# connect.net
KiCad netlist of a schematic drawn in Altium Designer
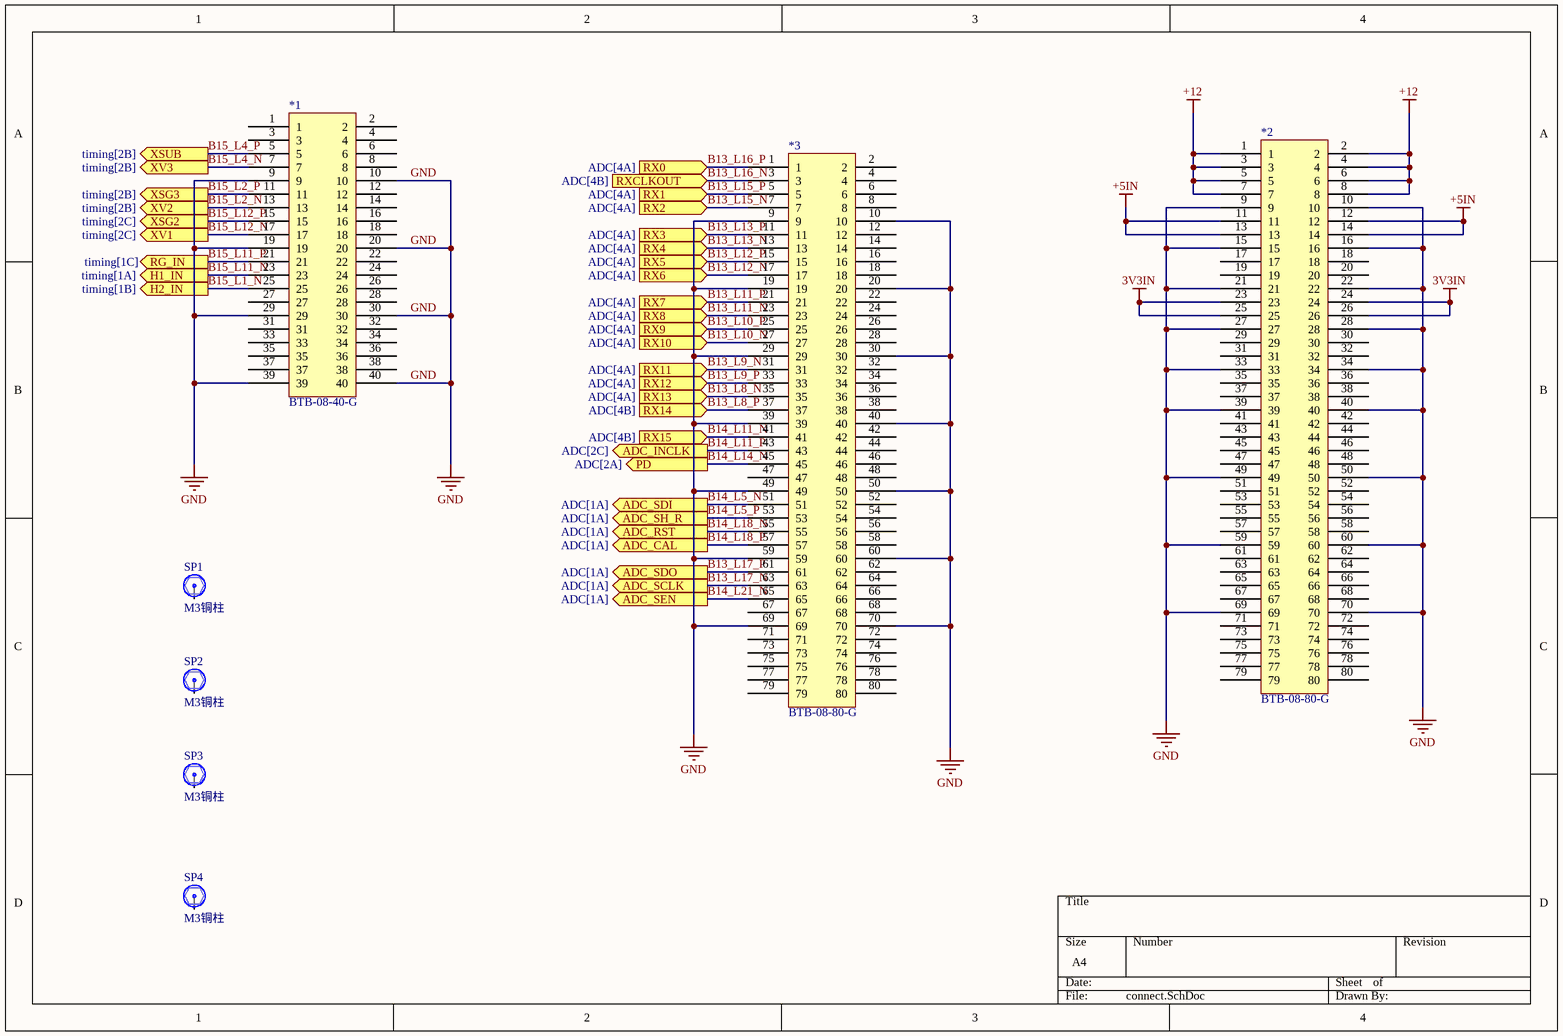
[diagram p0: connect.SchDoc]

(export (version "E")
  (design (tool "Eeschema 10.0.6"))
  (components
    (comp (ref "*1")
      (value "BTB-08-40-G")
      (footprint "BTB-08-40-M")
      (libsource (lib "0.04连接器") (part "BTB-08-40-G"))
    )
    (comp (ref "*2")
      (value "BTB-08-80-G")
      (footprint "BTB-08-80-G")
      (libsource (lib "0.04连接器") (part "BTB-08-80-G"))
    )
    (comp (ref "*3")
      (value "BTB-08-80-G")
      (footprint "BTB-08-80-G")
      (libsource (lib "0.04连接器") (part "BTB-08-80-G"))
    )
    (comp (ref "SP1")
      (value "M3铜柱")
      (footprint "M3x5_N")
      (description "铜柱")
      (fields (field (name "版权归属") "封装库来自淘宝 ID：黄晶宝石"))
      (libsource (lib "9.09-固定柱") (part "铜柱大焊盘"))
    )
    (comp (ref "SP2")
      (value "M3铜柱")
      (footprint "M3x5_N")
      (description "铜柱")
      (fields (field (name "版权归属") "封装库来自淘宝 ID：黄晶宝石"))
      (libsource (lib "9.09-固定柱") (part "铜柱大焊盘"))
    )
    (comp (ref "SP3")
      (value "M3铜柱")
      (footprint "M3x5_N")
      (description "铜柱")
      (fields (field (name "版权归属") "封装库来自淘宝 ID：黄晶宝石"))
      (libsource (lib "9.09-固定柱") (part "铜柱大焊盘"))
    )
    (comp (ref "SP4")
      (value "M3铜柱")
      (footprint "M3x5_N")
      (description "铜柱")
      (fields (field (name "版权归属") "封装库来自淘宝 ID：黄晶宝石"))
      (libsource (lib "9.09-固定柱") (part "铜柱大焊盘"))
    )
  )
  (nets
    (net (code "1") (name "+5IN") (class "Default")
      (node (ref "*2") (pin "11") (pinfunction "11_11") (pintype "passive"))
      (node (ref "*2") (pin "12") (pinfunction "12_12") (pintype "passive"))
      (node (ref "*2") (pin "13") (pinfunction "13_13") (pintype "passive"))
      (node (ref "*2") (pin "14") (pinfunction "14_14") (pintype "passive"))
    )
    (net (code "2") (name "+12") (class "Default")
      (node (ref "*2") (pin "1") (pinfunction "1_1") (pintype "passive"))
      (node (ref "*2") (pin "2") (pinfunction "2_2") (pintype "passive"))
      (node (ref "*2") (pin "3") (pinfunction "3_3") (pintype "passive"))
      (node (ref "*2") (pin "4") (pinfunction "4_4") (pintype "passive"))
      (node (ref "*2") (pin "5") (pinfunction "5_5") (pintype "passive"))
      (node (ref "*2") (pin "6") (pinfunction "6_6") (pintype "passive"))
      (node (ref "*2") (pin "7") (pinfunction "7_7") (pintype "passive"))
      (node (ref "*2") (pin "8") (pinfunction "8_8") (pintype "passive"))
    )
    (net (code "3") (name "/B13_L8_N") (class "Default")
      (node (ref "*3") (pin "35") (pinfunction "35_35") (pintype "passive"))
    )
    (net (code "4") (name "/B13_L8_P") (class "Default")
      (node (ref "*3") (pin "37") (pinfunction "37_37") (pintype "passive"))
    )
    (net (code "5") (name "/B13_L9_N") (class "Default")
      (node (ref "*3") (pin "31") (pinfunction "31_31") (pintype "passive"))
    )
    (net (code "6") (name "/B13_L9_P") (class "Default")
      (node (ref "*3") (pin "33") (pinfunction "33_33") (pintype "passive"))
    )
    (net (code "7") (name "/B13_L10_N") (class "Default")
      (node (ref "*3") (pin "27") (pinfunction "27_27") (pintype "passive"))
    )
    (net (code "8") (name "/B13_L10_P") (class "Default")
      (node (ref "*3") (pin "25") (pinfunction "25_25") (pintype "passive"))
    )
    (net (code "9") (name "/B13_L11_N") (class "Default")
      (node (ref "*3") (pin "23") (pinfunction "23_23") (pintype "passive"))
    )
    (net (code "10") (name "/B13_L11_P") (class "Default")
      (node (ref "*3") (pin "21") (pinfunction "21_21") (pintype "passive"))
    )
    (net (code "11") (name "/B13_L12_N") (class "Default")
      (node (ref "*3") (pin "17") (pinfunction "17_17") (pintype "passive"))
    )
    (net (code "12") (name "/B13_L12_P") (class "Default")
      (node (ref "*3") (pin "15") (pinfunction "15_15") (pintype "passive"))
    )
    (net (code "13") (name "/B13_L13_N") (class "Default")
      (node (ref "*3") (pin "13") (pinfunction "13_13") (pintype "passive"))
    )
    (net (code "14") (name "/B13_L13_P") (class "Default")
      (node (ref "*3") (pin "11") (pinfunction "11_11") (pintype "passive"))
    )
    (net (code "15") (name "/B13_L15_N") (class "Default")
      (node (ref "*3") (pin "7") (pinfunction "7_7") (pintype "passive"))
    )
    (net (code "16") (name "/B13_L15_P") (class "Default")
      (node (ref "*3") (pin "5") (pinfunction "5_5") (pintype "passive"))
    )
    (net (code "17") (name "/B13_L16_N") (class "Default")
      (node (ref "*3") (pin "3") (pinfunction "3_3") (pintype "passive"))
    )
    (net (code "18") (name "/B13_L16_P") (class "Default")
      (node (ref "*3") (pin "1") (pinfunction "1_1") (pintype "passive"))
    )
    (net (code "19") (name "/B13_L17_N") (class "Default")
      (node (ref "*3") (pin "63") (pinfunction "63_63") (pintype "passive"))
    )
    (net (code "20") (name "/B13_L17_P") (class "Default")
      (node (ref "*3") (pin "61") (pinfunction "61_61") (pintype "passive"))
    )
    (net (code "21") (name "/B14_L5_N") (class "Default")
      (node (ref "*3") (pin "51") (pinfunction "51_51") (pintype "passive"))
    )
    (net (code "22") (name "/B14_L5_P") (class "Default")
      (node (ref "*3") (pin "53") (pinfunction "53_53") (pintype "passive"))
    )
    (net (code "23") (name "/B14_L11_N") (class "Default")
      (node (ref "*3") (pin "41") (pinfunction "41_41") (pintype "passive"))
    )
    (net (code "24") (name "/B14_L11_P") (class "Default")
      (node (ref "*3") (pin "43") (pinfunction "43_43") (pintype "passive"))
    )
    (net (code "25") (name "/B14_L14_N") (class "Default")
      (node (ref "*3") (pin "45") (pinfunction "45_45") (pintype "passive"))
    )
    (net (code "26") (name "/B14_L18_N") (class "Default")
      (node (ref "*3") (pin "55") (pinfunction "55_55") (pintype "passive"))
    )
    (net (code "27") (name "/B14_L18_P") (class "Default")
      (node (ref "*3") (pin "57") (pinfunction "57_57") (pintype "passive"))
    )
    (net (code "28") (name "/B14_L21_N") (class "Default")
      (node (ref "*3") (pin "65") (pinfunction "65_65") (pintype "passive"))
    )
    (net (code "29") (name "/B15_L1_N") (class "Default")
      (node (ref "*1") (pin "25") (pinfunction "25_25") (pintype "passive"))
    )
    (net (code "30") (name "/B15_L2_N") (class "Default")
      (node (ref "*1") (pin "13") (pinfunction "13_13") (pintype "passive"))
    )
    (net (code "31") (name "/B15_L2_P") (class "Default")
      (node (ref "*1") (pin "11") (pinfunction "11_11") (pintype "passive"))
    )
    (net (code "32") (name "/B15_L4_N") (class "Default")
      (node (ref "*1") (pin "7") (pinfunction "7_7") (pintype "passive"))
    )
    (net (code "33") (name "/B15_L4_P") (class "Default")
      (node (ref "*1") (pin "5") (pinfunction "5_5") (pintype "passive"))
    )
    (net (code "34") (name "/B15_L11_N") (class "Default")
      (node (ref "*1") (pin "23") (pinfunction "23_23") (pintype "passive"))
    )
    (net (code "35") (name "/B15_L11_P") (class "Default")
      (node (ref "*1") (pin "21") (pinfunction "21_21") (pintype "passive"))
    )
    (net (code "36") (name "/B15_L12_N") (class "Default")
      (node (ref "*1") (pin "17") (pinfunction "17_17") (pintype "passive"))
    )
    (net (code "37") (name "/B15_L12_P") (class "Default")
      (node (ref "*1") (pin "15") (pinfunction "15_15") (pintype "passive"))
    )
    (net (code "38") (name "3V3IN") (class "Default")
      (node (ref "*2") (pin "23") (pinfunction "23_23") (pintype "passive"))
      (node (ref "*2") (pin "24") (pinfunction "24_24") (pintype "passive"))
      (node (ref "*2") (pin "25") (pinfunction "25_25") (pintype "passive"))
      (node (ref "*2") (pin "26") (pinfunction "26_26") (pintype "passive"))
    )
    (net (code "39") (name "GND") (class "Default")
      (node (ref "*1") (pin "10") (pinfunction "10_10") (pintype "passive"))
      (node (ref "*1") (pin "19") (pinfunction "19_19") (pintype "passive"))
      (node (ref "*1") (pin "20") (pinfunction "20_20") (pintype "passive"))
      (node (ref "*1") (pin "29") (pinfunction "29_29") (pintype "passive"))
      (node (ref "*1") (pin "30") (pinfunction "30_30") (pintype "passive"))
      (node (ref "*1") (pin "39") (pinfunction "39_39") (pintype "passive"))
      (node (ref "*1") (pin "40") (pinfunction "40_40") (pintype "passive"))
      (node (ref "*1") (pin "9") (pinfunction "9_9") (pintype "passive"))
      (node (ref "*2") (pin "10") (pinfunction "10_10") (pintype "passive"))
      (node (ref "*2") (pin "15") (pinfunction "15_15") (pintype "passive"))
      (node (ref "*2") (pin "16") (pinfunction "16_16") (pintype "passive"))
      (node (ref "*2") (pin "21") (pinfunction "21_21") (pintype "passive"))
      (node (ref "*2") (pin "22") (pinfunction "22_22") (pintype "passive"))
      (node (ref "*2") (pin "27") (pinfunction "27_27") (pintype "passive"))
      (node (ref "*2") (pin "28") (pinfunction "28_28") (pintype "passive"))
      (node (ref "*2") (pin "33") (pinfunction "33_33") (pintype "passive"))
      (node (ref "*2") (pin "34") (pinfunction "34_34") (pintype "passive"))
      (node (ref "*2") (pin "39") (pinfunction "39_39") (pintype "passive"))
      (node (ref "*2") (pin "40") (pinfunction "40_40") (pintype "passive"))
      (node (ref "*2") (pin "49") (pinfunction "49_49") (pintype "passive"))
      (node (ref "*2") (pin "50") (pinfunction "50_50") (pintype "passive"))
      (node (ref "*2") (pin "59") (pinfunction "59_59") (pintype "passive"))
      (node (ref "*2") (pin "60") (pinfunction "60_60") (pintype "passive"))
      (node (ref "*2") (pin "69") (pinfunction "69_69") (pintype "passive"))
      (node (ref "*2") (pin "70") (pinfunction "70_70") (pintype "passive"))
      (node (ref "*2") (pin "9") (pinfunction "9_9") (pintype "passive"))
      (node (ref "*3") (pin "10") (pinfunction "10_10") (pintype "passive"))
      (node (ref "*3") (pin "19") (pinfunction "19_19") (pintype "passive"))
      (node (ref "*3") (pin "20") (pinfunction "20_20") (pintype "passive"))
      (node (ref "*3") (pin "29") (pinfunction "29_29") (pintype "passive"))
      (node (ref "*3") (pin "30") (pinfunction "30_30") (pintype "passive"))
      (node (ref "*3") (pin "39") (pinfunction "39_39") (pintype "passive"))
      (node (ref "*3") (pin "40") (pinfunction "40_40") (pintype "passive"))
      (node (ref "*3") (pin "49") (pinfunction "49_49") (pintype "passive"))
      (node (ref "*3") (pin "50") (pinfunction "50_50") (pintype "passive"))
      (node (ref "*3") (pin "59") (pinfunction "59_59") (pintype "passive"))
      (node (ref "*3") (pin "60") (pinfunction "60_60") (pintype "passive"))
      (node (ref "*3") (pin "69") (pinfunction "69_69") (pintype "passive"))
      (node (ref "*3") (pin "70") (pinfunction "70_70") (pintype "passive"))
      (node (ref "*3") (pin "9") (pinfunction "9_9") (pintype "passive"))
    )
    (net (code "40") (name "unconnected-(*1-Pad1)") (class "Default")
      (node (ref "*1") (pin "1") (pinfunction "1_1") (pintype "passive"))
    )
    (net (code "41") (name "unconnected-(*1-Pad2)") (class "Default")
      (node (ref "*1") (pin "2") (pinfunction "2_2") (pintype "passive"))
    )
    (net (code "42") (name "unconnected-(*1-Pad3)") (class "Default")
      (node (ref "*1") (pin "3") (pinfunction "3_3") (pintype "passive"))
    )
    (net (code "43") (name "unconnected-(*1-Pad4)") (class "Default")
      (node (ref "*1") (pin "4") (pinfunction "4_4") (pintype "passive"))
    )
    (net (code "44") (name "unconnected-(*1-Pad6)") (class "Default")
      (node (ref "*1") (pin "6") (pinfunction "6_6") (pintype "passive"))
    )
    (net (code "45") (name "unconnected-(*1-Pad8)") (class "Default")
      (node (ref "*1") (pin "8") (pinfunction "8_8") (pintype "passive"))
    )
    (net (code "46") (name "unconnected-(*1-Pad12)") (class "Default")
      (node (ref "*1") (pin "12") (pinfunction "12_12") (pintype "passive"))
    )
    (net (code "47") (name "unconnected-(*1-Pad14)") (class "Default")
      (node (ref "*1") (pin "14") (pinfunction "14_14") (pintype "passive"))
    )
    (net (code "48") (name "unconnected-(*1-Pad16)") (class "Default")
      (node (ref "*1") (pin "16") (pinfunction "16_16") (pintype "passive"))
    )
    (net (code "49") (name "unconnected-(*1-Pad18)") (class "Default")
      (node (ref "*1") (pin "18") (pinfunction "18_18") (pintype "passive"))
    )
    (net (code "50") (name "unconnected-(*1-Pad22)") (class "Default")
      (node (ref "*1") (pin "22") (pinfunction "22_22") (pintype "passive"))
    )
    (net (code "51") (name "unconnected-(*1-Pad24)") (class "Default")
      (node (ref "*1") (pin "24") (pinfunction "24_24") (pintype "passive"))
    )
    (net (code "52") (name "unconnected-(*1-Pad26)") (class "Default")
      (node (ref "*1") (pin "26") (pinfunction "26_26") (pintype "passive"))
    )
    (net (code "53") (name "unconnected-(*1-Pad27)") (class "Default")
      (node (ref "*1") (pin "27") (pinfunction "27_27") (pintype "passive"))
    )
    (net (code "54") (name "unconnected-(*1-Pad28)") (class "Default")
      (node (ref "*1") (pin "28") (pinfunction "28_28") (pintype "passive"))
    )
    (net (code "55") (name "unconnected-(*1-Pad31)") (class "Default")
      (node (ref "*1") (pin "31") (pinfunction "31_31") (pintype "passive"))
    )
    (net (code "56") (name "unconnected-(*1-Pad32)") (class "Default")
      (node (ref "*1") (pin "32") (pinfunction "32_32") (pintype "passive"))
    )
    (net (code "57") (name "unconnected-(*1-Pad33)") (class "Default")
      (node (ref "*1") (pin "33") (pinfunction "33_33") (pintype "passive"))
    )
    (net (code "58") (name "unconnected-(*1-Pad34)") (class "Default")
      (node (ref "*1") (pin "34") (pinfunction "34_34") (pintype "passive"))
    )
    (net (code "59") (name "unconnected-(*1-Pad35)") (class "Default")
      (node (ref "*1") (pin "35") (pinfunction "35_35") (pintype "passive"))
    )
    (net (code "60") (name "unconnected-(*1-Pad36)") (class "Default")
      (node (ref "*1") (pin "36") (pinfunction "36_36") (pintype "passive"))
    )
    (net (code "61") (name "unconnected-(*1-Pad37)") (class "Default")
      (node (ref "*1") (pin "37") (pinfunction "37_37") (pintype "passive"))
    )
    (net (code "62") (name "unconnected-(*1-Pad38)") (class "Default")
      (node (ref "*1") (pin "38") (pinfunction "38_38") (pintype "passive"))
    )
    (net (code "63") (name "unconnected-(*2-Pad17)") (class "Default")
      (node (ref "*2") (pin "17") (pinfunction "17_17") (pintype "passive"))
    )
    (net (code "64") (name "unconnected-(*2-Pad18)") (class "Default")
      (node (ref "*2") (pin "18") (pinfunction "18_18") (pintype "passive"))
    )
    (net (code "65") (name "unconnected-(*2-Pad19)") (class "Default")
      (node (ref "*2") (pin "19") (pinfunction "19_19") (pintype "passive"))
    )
    (net (code "66") (name "unconnected-(*2-Pad20)") (class "Default")
      (node (ref "*2") (pin "20") (pinfunction "20_20") (pintype "passive"))
    )
    (net (code "67") (name "unconnected-(*2-Pad29)") (class "Default")
      (node (ref "*2") (pin "29") (pinfunction "29_29") (pintype "passive"))
    )
    (net (code "68") (name "unconnected-(*2-Pad30)") (class "Default")
      (node (ref "*2") (pin "30") (pinfunction "30_30") (pintype "passive"))
    )
    (net (code "69") (name "unconnected-(*2-Pad31)") (class "Default")
      (node (ref "*2") (pin "31") (pinfunction "31_31") (pintype "passive"))
    )
    (net (code "70") (name "unconnected-(*2-Pad32)") (class "Default")
      (node (ref "*2") (pin "32") (pinfunction "32_32") (pintype "passive"))
    )
    (net (code "71") (name "unconnected-(*2-Pad35)") (class "Default")
      (node (ref "*2") (pin "35") (pinfunction "35_35") (pintype "passive"))
    )
    (net (code "72") (name "unconnected-(*2-Pad36)") (class "Default")
      (node (ref "*2") (pin "36") (pinfunction "36_36") (pintype "passive"))
    )
    (net (code "73") (name "unconnected-(*2-Pad37)") (class "Default")
      (node (ref "*2") (pin "37") (pinfunction "37_37") (pintype "passive"))
    )
    (net (code "74") (name "unconnected-(*2-Pad38)") (class "Default")
      (node (ref "*2") (pin "38") (pinfunction "38_38") (pintype "passive"))
    )
    (net (code "75") (name "unconnected-(*2-Pad41)") (class "Default")
      (node (ref "*2") (pin "41") (pinfunction "41_41") (pintype "passive"))
    )
    (net (code "76") (name "unconnected-(*2-Pad42)") (class "Default")
      (node (ref "*2") (pin "42") (pinfunction "42_42") (pintype "passive"))
    )
    (net (code "77") (name "unconnected-(*2-Pad43)") (class "Default")
      (node (ref "*2") (pin "43") (pinfunction "43_43") (pintype "passive"))
    )
    (net (code "78") (name "unconnected-(*2-Pad44)") (class "Default")
      (node (ref "*2") (pin "44") (pinfunction "44_44") (pintype "passive"))
    )
    (net (code "79") (name "unconnected-(*2-Pad45)") (class "Default")
      (node (ref "*2") (pin "45") (pinfunction "45_45") (pintype "passive"))
    )
    (net (code "80") (name "unconnected-(*2-Pad46)") (class "Default")
      (node (ref "*2") (pin "46") (pinfunction "46_46") (pintype "passive"))
    )
    (net (code "81") (name "unconnected-(*2-Pad47)") (class "Default")
      (node (ref "*2") (pin "47") (pinfunction "47_47") (pintype "passive"))
    )
    (net (code "82") (name "unconnected-(*2-Pad48)") (class "Default")
      (node (ref "*2") (pin "48") (pinfunction "48_48") (pintype "passive"))
    )
    (net (code "83") (name "unconnected-(*2-Pad51)") (class "Default")
      (node (ref "*2") (pin "51") (pinfunction "51_51") (pintype "passive"))
    )
    (net (code "84") (name "unconnected-(*2-Pad52)") (class "Default")
      (node (ref "*2") (pin "52") (pinfunction "52_52") (pintype "passive"))
    )
    (net (code "85") (name "unconnected-(*2-Pad53)") (class "Default")
      (node (ref "*2") (pin "53") (pinfunction "53_53") (pintype "passive"))
    )
    (net (code "86") (name "unconnected-(*2-Pad54)") (class "Default")
      (node (ref "*2") (pin "54") (pinfunction "54_54") (pintype "passive"))
    )
    (net (code "87") (name "unconnected-(*2-Pad55)") (class "Default")
      (node (ref "*2") (pin "55") (pinfunction "55_55") (pintype "passive"))
    )
    (net (code "88") (name "unconnected-(*2-Pad56)") (class "Default")
      (node (ref "*2") (pin "56") (pinfunction "56_56") (pintype "passive"))
    )
    (net (code "89") (name "unconnected-(*2-Pad57)") (class "Default")
      (node (ref "*2") (pin "57") (pinfunction "57_57") (pintype "passive"))
    )
    (net (code "90") (name "unconnected-(*2-Pad58)") (class "Default")
      (node (ref "*2") (pin "58") (pinfunction "58_58") (pintype "passive"))
    )
    (net (code "91") (name "unconnected-(*2-Pad61)") (class "Default")
      (node (ref "*2") (pin "61") (pinfunction "61_61") (pintype "passive"))
    )
    (net (code "92") (name "unconnected-(*2-Pad62)") (class "Default")
      (node (ref "*2") (pin "62") (pinfunction "62_62") (pintype "passive"))
    )
    (net (code "93") (name "unconnected-(*2-Pad63)") (class "Default")
      (node (ref "*2") (pin "63") (pinfunction "63_63") (pintype "passive"))
    )
    (net (code "94") (name "unconnected-(*2-Pad64)") (class "Default")
      (node (ref "*2") (pin "64") (pinfunction "64_64") (pintype "passive"))
    )
    (net (code "95") (name "unconnected-(*2-Pad65)") (class "Default")
      (node (ref "*2") (pin "65") (pinfunction "65_65") (pintype "passive"))
    )
    (net (code "96") (name "unconnected-(*2-Pad66)") (class "Default")
      (node (ref "*2") (pin "66") (pinfunction "66_66") (pintype "passive"))
    )
    (net (code "97") (name "unconnected-(*2-Pad67)") (class "Default")
      (node (ref "*2") (pin "67") (pinfunction "67_67") (pintype "passive"))
    )
    (net (code "98") (name "unconnected-(*2-Pad68)") (class "Default")
      (node (ref "*2") (pin "68") (pinfunction "68_68") (pintype "passive"))
    )
    (net (code "99") (name "unconnected-(*2-Pad71)") (class "Default")
      (node (ref "*2") (pin "71") (pinfunction "71_71") (pintype "passive"))
    )
    (net (code "100") (name "unconnected-(*2-Pad72)") (class "Default")
      (node (ref "*2") (pin "72") (pinfunction "72_72") (pintype "passive"))
    )
    (net (code "101") (name "unconnected-(*2-Pad73)") (class "Default")
      (node (ref "*2") (pin "73") (pinfunction "73_73") (pintype "passive"))
    )
    (net (code "102") (name "unconnected-(*2-Pad74)") (class "Default")
      (node (ref "*2") (pin "74") (pinfunction "74_74") (pintype "passive"))
    )
    (net (code "103") (name "unconnected-(*2-Pad75)") (class "Default")
      (node (ref "*2") (pin "75") (pinfunction "75_75") (pintype "passive"))
    )
    (net (code "104") (name "unconnected-(*2-Pad76)") (class "Default")
      (node (ref "*2") (pin "76") (pinfunction "76_76") (pintype "passive"))
    )
    (net (code "105") (name "unconnected-(*2-Pad77)") (class "Default")
      (node (ref "*2") (pin "77") (pinfunction "77_77") (pintype "passive"))
    )
    (net (code "106") (name "unconnected-(*2-Pad78)") (class "Default")
      (node (ref "*2") (pin "78") (pinfunction "78_78") (pintype "passive"))
    )
    (net (code "107") (name "unconnected-(*2-Pad79)") (class "Default")
      (node (ref "*2") (pin "79") (pinfunction "79_79") (pintype "passive"))
    )
    (net (code "108") (name "unconnected-(*2-Pad80)") (class "Default")
      (node (ref "*2") (pin "80") (pinfunction "80_80") (pintype "passive"))
    )
    (net (code "109") (name "unconnected-(*3-Pad2)") (class "Default")
      (node (ref "*3") (pin "2") (pinfunction "2_2") (pintype "passive"))
    )
    (net (code "110") (name "unconnected-(*3-Pad4)") (class "Default")
      (node (ref "*3") (pin "4") (pinfunction "4_4") (pintype "passive"))
    )
    (net (code "111") (name "unconnected-(*3-Pad6)") (class "Default")
      (node (ref "*3") (pin "6") (pinfunction "6_6") (pintype "passive"))
    )
    (net (code "112") (name "unconnected-(*3-Pad8)") (class "Default")
      (node (ref "*3") (pin "8") (pinfunction "8_8") (pintype "passive"))
    )
    (net (code "113") (name "unconnected-(*3-Pad12)") (class "Default")
      (node (ref "*3") (pin "12") (pinfunction "12_12") (pintype "passive"))
    )
    (net (code "114") (name "unconnected-(*3-Pad14)") (class "Default")
      (node (ref "*3") (pin "14") (pinfunction "14_14") (pintype "passive"))
    )
    (net (code "115") (name "unconnected-(*3-Pad16)") (class "Default")
      (node (ref "*3") (pin "16") (pinfunction "16_16") (pintype "passive"))
    )
    (net (code "116") (name "unconnected-(*3-Pad18)") (class "Default")
      (node (ref "*3") (pin "18") (pinfunction "18_18") (pintype "passive"))
    )
    (net (code "117") (name "unconnected-(*3-Pad22)") (class "Default")
      (node (ref "*3") (pin "22") (pinfunction "22_22") (pintype "passive"))
    )
    (net (code "118") (name "unconnected-(*3-Pad24)") (class "Default")
      (node (ref "*3") (pin "24") (pinfunction "24_24") (pintype "passive"))
    )
    (net (code "119") (name "unconnected-(*3-Pad26)") (class "Default")
      (node (ref "*3") (pin "26") (pinfunction "26_26") (pintype "passive"))
    )
    (net (code "120") (name "unconnected-(*3-Pad28)") (class "Default")
      (node (ref "*3") (pin "28") (pinfunction "28_28") (pintype "passive"))
    )
    (net (code "121") (name "unconnected-(*3-Pad32)") (class "Default")
      (node (ref "*3") (pin "32") (pinfunction "32_32") (pintype "passive"))
    )
    (net (code "122") (name "unconnected-(*3-Pad34)") (class "Default")
      (node (ref "*3") (pin "34") (pinfunction "34_34") (pintype "passive"))
    )
    (net (code "123") (name "unconnected-(*3-Pad36)") (class "Default")
      (node (ref "*3") (pin "36") (pinfunction "36_36") (pintype "passive"))
    )
    (net (code "124") (name "unconnected-(*3-Pad38)") (class "Default")
      (node (ref "*3") (pin "38") (pinfunction "38_38") (pintype "passive"))
    )
    (net (code "125") (name "unconnected-(*3-Pad42)") (class "Default")
      (node (ref "*3") (pin "42") (pinfunction "42_42") (pintype "passive"))
    )
    (net (code "126") (name "unconnected-(*3-Pad44)") (class "Default")
      (node (ref "*3") (pin "44") (pinfunction "44_44") (pintype "passive"))
    )
    (net (code "127") (name "unconnected-(*3-Pad46)") (class "Default")
      (node (ref "*3") (pin "46") (pinfunction "46_46") (pintype "passive"))
    )
    (net (code "128") (name "unconnected-(*3-Pad47)") (class "Default")
      (node (ref "*3") (pin "47") (pinfunction "47_47") (pintype "passive"))
    )
    (net (code "129") (name "unconnected-(*3-Pad48)") (class "Default")
      (node (ref "*3") (pin "48") (pinfunction "48_48") (pintype "passive"))
    )
    (net (code "130") (name "unconnected-(*3-Pad52)") (class "Default")
      (node (ref "*3") (pin "52") (pinfunction "52_52") (pintype "passive"))
    )
    (net (code "131") (name "unconnected-(*3-Pad54)") (class "Default")
      (node (ref "*3") (pin "54") (pinfunction "54_54") (pintype "passive"))
    )
    (net (code "132") (name "unconnected-(*3-Pad56)") (class "Default")
      (node (ref "*3") (pin "56") (pinfunction "56_56") (pintype "passive"))
    )
    (net (code "133") (name "unconnected-(*3-Pad58)") (class "Default")
      (node (ref "*3") (pin "58") (pinfunction "58_58") (pintype "passive"))
    )
    (net (code "134") (name "unconnected-(*3-Pad62)") (class "Default")
      (node (ref "*3") (pin "62") (pinfunction "62_62") (pintype "passive"))
    )
    (net (code "135") (name "unconnected-(*3-Pad64)") (class "Default")
      (node (ref "*3") (pin "64") (pinfunction "64_64") (pintype "passive"))
    )
    (net (code "136") (name "unconnected-(*3-Pad66)") (class "Default")
      (node (ref "*3") (pin "66") (pinfunction "66_66") (pintype "passive"))
    )
    (net (code "137") (name "unconnected-(*3-Pad67)") (class "Default")
      (node (ref "*3") (pin "67") (pinfunction "67_67") (pintype "passive"))
    )
    (net (code "138") (name "unconnected-(*3-Pad68)") (class "Default")
      (node (ref "*3") (pin "68") (pinfunction "68_68") (pintype "passive"))
    )
    (net (code "139") (name "unconnected-(*3-Pad71)") (class "Default")
      (node (ref "*3") (pin "71") (pinfunction "71_71") (pintype "passive"))
    )
    (net (code "140") (name "unconnected-(*3-Pad72)") (class "Default")
      (node (ref "*3") (pin "72") (pinfunction "72_72") (pintype "passive"))
    )
    (net (code "141") (name "unconnected-(*3-Pad73)") (class "Default")
      (node (ref "*3") (pin "73") (pinfunction "73_73") (pintype "passive"))
    )
    (net (code "142") (name "unconnected-(*3-Pad74)") (class "Default")
      (node (ref "*3") (pin "74") (pinfunction "74_74") (pintype "passive"))
    )
    (net (code "143") (name "unconnected-(*3-Pad75)") (class "Default")
      (node (ref "*3") (pin "75") (pinfunction "75_75") (pintype "passive"))
    )
    (net (code "144") (name "unconnected-(*3-Pad76)") (class "Default")
      (node (ref "*3") (pin "76") (pinfunction "76_76") (pintype "passive"))
    )
    (net (code "145") (name "unconnected-(*3-Pad77)") (class "Default")
      (node (ref "*3") (pin "77") (pinfunction "77_77") (pintype "passive"))
    )
    (net (code "146") (name "unconnected-(*3-Pad78)") (class "Default")
      (node (ref "*3") (pin "78") (pinfunction "78_78") (pintype "passive"))
    )
    (net (code "147") (name "unconnected-(*3-Pad79)") (class "Default")
      (node (ref "*3") (pin "79") (pinfunction "79_79") (pintype "passive"))
    )
    (net (code "148") (name "unconnected-(*3-Pad80)") (class "Default")
      (node (ref "*3") (pin "80") (pinfunction "80_80") (pintype "passive"))
    )
    (net (code "149") (name "unconnected-(SP1-Pad1)") (class "Default")
      (node (ref "SP1") (pin "1") (pinfunction "1_1") (pintype "passive"))
    )
    (net (code "150") (name "unconnected-(SP2-Pad1)") (class "Default")
      (node (ref "SP2") (pin "1") (pinfunction "1_1") (pintype "passive"))
    )
    (net (code "151") (name "unconnected-(SP3-Pad1)") (class "Default")
      (node (ref "SP3") (pin "1") (pinfunction "1_1") (pintype "passive"))
    )
    (net (code "152") (name "unconnected-(SP4-Pad1)") (class "Default")
      (node (ref "SP4") (pin "1") (pinfunction "1_1") (pintype "passive"))
    )
  )
)
